# D_OUTPUT_RELAY.net
KiCad netlist of a schematic drawn in Altium Designer
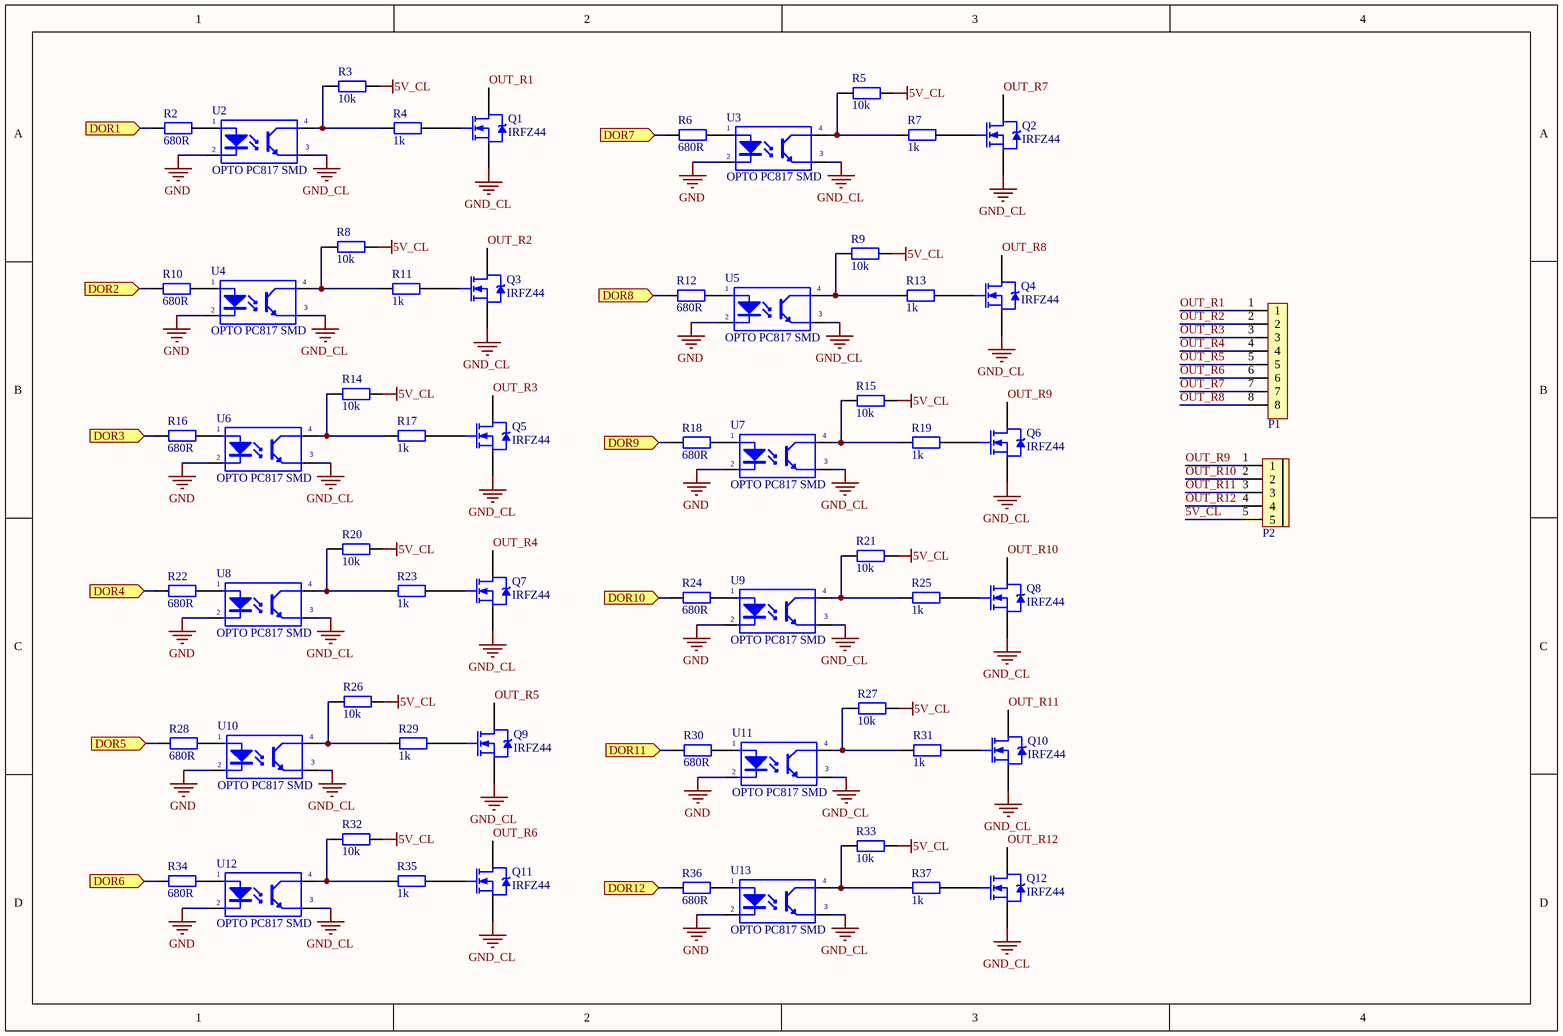
[diagram p0: D_OUTPUT_RELAY.SchDoc]

(export (version "E")
  (design (tool "Eeschema 10.0.6"))
  (components
    (comp (ref "P1")
      (value "CON 8 EDG5.08")
      (footprint "CON 8 8EDG5.08")
      (description "Cắm")
      (libsource (lib "Altium_Lib_by_KhueNguyenCreator") (part "CON 8 EDG5.08"))
    )
    (comp (ref "P2")
      (value "CON 5 EDG5.08")
      (footprint "CON 5 5EDG5.08")
      (description "Cắm")
      (libsource (lib "Altium_Lib_by_KhueNguyenCreator") (part "CON 5 EDG5.08"))
    )
    (comp (ref "Q1")
      (value "IRFZ44")
      (footprint "TO220")
      (description "N-Channel Power MOSFET")
      (libsource (lib "Altium_Lib_by_KhueNguyenCreator") (part "IRFZ44 DIP"))
    )
    (comp (ref "Q2")
      (value "IRFZ44")
      (footprint "TO220")
      (description "N-Channel Power MOSFET")
      (libsource (lib "Altium_Lib_by_KhueNguyenCreator") (part "IRFZ44 DIP"))
    )
    (comp (ref "Q3")
      (value "IRFZ44")
      (footprint "TO220")
      (description "N-Channel Power MOSFET")
      (libsource (lib "Altium_Lib_by_KhueNguyenCreator") (part "IRFZ44 DIP"))
    )
    (comp (ref "Q4")
      (value "IRFZ44")
      (footprint "TO220")
      (description "N-Channel Power MOSFET")
      (libsource (lib "Altium_Lib_by_KhueNguyenCreator") (part "IRFZ44 DIP"))
    )
    (comp (ref "Q5")
      (value "IRFZ44")
      (footprint "TO220")
      (description "N-Channel Power MOSFET")
      (libsource (lib "Altium_Lib_by_KhueNguyenCreator") (part "IRFZ44 DIP"))
    )
    (comp (ref "Q6")
      (value "IRFZ44")
      (footprint "TO220")
      (description "N-Channel Power MOSFET")
      (libsource (lib "Altium_Lib_by_KhueNguyenCreator") (part "IRFZ44 DIP"))
    )
    (comp (ref "Q7")
      (value "IRFZ44")
      (footprint "TO220")
      (description "N-Channel Power MOSFET")
      (libsource (lib "Altium_Lib_by_KhueNguyenCreator") (part "IRFZ44 DIP"))
    )
    (comp (ref "Q8")
      (value "IRFZ44")
      (footprint "TO220")
      (description "N-Channel Power MOSFET")
      (libsource (lib "Altium_Lib_by_KhueNguyenCreator") (part "IRFZ44 DIP"))
    )
    (comp (ref "Q9")
      (value "IRFZ44")
      (footprint "TO220")
      (description "N-Channel Power MOSFET")
      (libsource (lib "Altium_Lib_by_KhueNguyenCreator") (part "IRFZ44 DIP"))
    )
    (comp (ref "Q10")
      (value "IRFZ44")
      (footprint "TO220")
      (description "N-Channel Power MOSFET")
      (libsource (lib "Altium_Lib_by_KhueNguyenCreator") (part "IRFZ44 DIP"))
    )
    (comp (ref "Q11")
      (value "IRFZ44")
      (footprint "TO220")
      (description "N-Channel Power MOSFET")
      (libsource (lib "Altium_Lib_by_KhueNguyenCreator") (part "IRFZ44 DIP"))
    )
    (comp (ref "Q12")
      (value "IRFZ44")
      (footprint "TO220")
      (description "N-Channel Power MOSFET")
      (libsource (lib "Altium_Lib_by_KhueNguyenCreator") (part "IRFZ44 DIP"))
    )
    (comp (ref "R2")
      (value "680R")
      (footprint "tro smd 0805")
      (description "Dán")
      (libsource (lib "Altium_Lib_by_KhueNguyenCreator") (part "Tro 0805 1% 680R"))
    )
    (comp (ref "R3")
      (value "10k")
      (footprint "tro smd 0805")
      (description "Dán")
      (libsource (lib "Altium_Lib_by_KhueNguyenCreator") (part "Tro 0805 1% 10k"))
    )
    (comp (ref "R4")
      (value "1k")
      (footprint "tro smd 0805")
      (description "Dán")
      (libsource (lib "Altium_Lib_by_KhueNguyenCreator") (part "Tro 0805 1% 1k"))
    )
    (comp (ref "R5")
      (value "10k")
      (footprint "tro smd 0805")
      (description "Dán")
      (libsource (lib "Altium_Lib_by_KhueNguyenCreator") (part "Tro 0805 1% 10k"))
    )
    (comp (ref "R6")
      (value "680R")
      (footprint "tro smd 0805")
      (description "Dán")
      (libsource (lib "Altium_Lib_by_KhueNguyenCreator") (part "Tro 0805 1% 680R"))
    )
    (comp (ref "R7")
      (value "1k")
      (footprint "tro smd 0805")
      (description "Dán")
      (libsource (lib "Altium_Lib_by_KhueNguyenCreator") (part "Tro 0805 1% 1k"))
    )
    (comp (ref "R8")
      (value "10k")
      (footprint "tro smd 0805")
      (description "Dán")
      (libsource (lib "Altium_Lib_by_KhueNguyenCreator") (part "Tro 0805 1% 10k"))
    )
    (comp (ref "R9")
      (value "10k")
      (footprint "tro smd 0805")
      (description "Dán")
      (libsource (lib "Altium_Lib_by_KhueNguyenCreator") (part "Tro 0805 1% 10k"))
    )
    (comp (ref "R10")
      (value "680R")
      (footprint "tro smd 0805")
      (description "Dán")
      (libsource (lib "Altium_Lib_by_KhueNguyenCreator") (part "Tro 0805 1% 680R"))
    )
    (comp (ref "R11")
      (value "1k")
      (footprint "tro smd 0805")
      (description "Dán")
      (libsource (lib "Altium_Lib_by_KhueNguyenCreator") (part "Tro 0805 1% 1k"))
    )
    (comp (ref "R12")
      (value "680R")
      (footprint "tro smd 0805")
      (description "Dán")
      (libsource (lib "Altium_Lib_by_KhueNguyenCreator") (part "Tro 0805 1% 680R"))
    )
    (comp (ref "R13")
      (value "1k")
      (footprint "tro smd 0805")
      (description "Dán")
      (libsource (lib "Altium_Lib_by_KhueNguyenCreator") (part "Tro 0805 1% 1k"))
    )
    (comp (ref "R14")
      (value "10k")
      (footprint "tro smd 0805")
      (description "Dán")
      (libsource (lib "Altium_Lib_by_KhueNguyenCreator") (part "Tro 0805 1% 10k"))
    )
    (comp (ref "R15")
      (value "10k")
      (footprint "tro smd 0805")
      (description "Dán")
      (libsource (lib "Altium_Lib_by_KhueNguyenCreator") (part "Tro 0805 1% 10k"))
    )
    (comp (ref "R16")
      (value "680R")
      (footprint "tro smd 0805")
      (description "Dán")
      (libsource (lib "Altium_Lib_by_KhueNguyenCreator") (part "Tro 0805 1% 680R"))
    )
    (comp (ref "R17")
      (value "1k")
      (footprint "tro smd 0805")
      (description "Dán")
      (libsource (lib "Altium_Lib_by_KhueNguyenCreator") (part "Tro 0805 1% 1k"))
    )
    (comp (ref "R18")
      (value "680R")
      (footprint "tro smd 0805")
      (description "Dán")
      (libsource (lib "Altium_Lib_by_KhueNguyenCreator") (part "Tro 0805 1% 680R"))
    )
    (comp (ref "R19")
      (value "1k")
      (footprint "tro smd 0805")
      (description "Dán")
      (libsource (lib "Altium_Lib_by_KhueNguyenCreator") (part "Tro 0805 1% 1k"))
    )
    (comp (ref "R20")
      (value "10k")
      (footprint "tro smd 0805")
      (description "Dán")
      (libsource (lib "Altium_Lib_by_KhueNguyenCreator") (part "Tro 0805 1% 10k"))
    )
    (comp (ref "R21")
      (value "10k")
      (footprint "tro smd 0805")
      (description "Dán")
      (libsource (lib "Altium_Lib_by_KhueNguyenCreator") (part "Tro 0805 1% 10k"))
    )
    (comp (ref "R22")
      (value "680R")
      (footprint "tro smd 0805")
      (description "Dán")
      (libsource (lib "Altium_Lib_by_KhueNguyenCreator") (part "Tro 0805 1% 680R"))
    )
    (comp (ref "R23")
      (value "1k")
      (footprint "tro smd 0805")
      (description "Dán")
      (libsource (lib "Altium_Lib_by_KhueNguyenCreator") (part "Tro 0805 1% 1k"))
    )
    (comp (ref "R24")
      (value "680R")
      (footprint "tro smd 0805")
      (description "Dán")
      (libsource (lib "Altium_Lib_by_KhueNguyenCreator") (part "Tro 0805 1% 680R"))
    )
    (comp (ref "R25")
      (value "1k")
      (footprint "tro smd 0805")
      (description "Dán")
      (libsource (lib "Altium_Lib_by_KhueNguyenCreator") (part "Tro 0805 1% 1k"))
    )
    (comp (ref "R26")
      (value "10k")
      (footprint "tro smd 0805")
      (description "Dán")
      (libsource (lib "Altium_Lib_by_KhueNguyenCreator") (part "Tro 0805 1% 10k"))
    )
    (comp (ref "R27")
      (value "10k")
      (footprint "tro smd 0805")
      (description "Dán")
      (libsource (lib "Altium_Lib_by_KhueNguyenCreator") (part "Tro 0805 1% 10k"))
    )
    (comp (ref "R28")
      (value "680R")
      (footprint "tro smd 0805")
      (description "Dán")
      (libsource (lib "Altium_Lib_by_KhueNguyenCreator") (part "Tro 0805 1% 680R"))
    )
    (comp (ref "R29")
      (value "1k")
      (footprint "tro smd 0805")
      (description "Dán")
      (libsource (lib "Altium_Lib_by_KhueNguyenCreator") (part "Tro 0805 1% 1k"))
    )
    (comp (ref "R30")
      (value "680R")
      (footprint "tro smd 0805")
      (description "Dán")
      (libsource (lib "Altium_Lib_by_KhueNguyenCreator") (part "Tro 0805 1% 680R"))
    )
    (comp (ref "R31")
      (value "1k")
      (footprint "tro smd 0805")
      (description "Dán")
      (libsource (lib "Altium_Lib_by_KhueNguyenCreator") (part "Tro 0805 1% 1k"))
    )
    (comp (ref "R32")
      (value "10k")
      (footprint "tro smd 0805")
      (description "Dán")
      (libsource (lib "Altium_Lib_by_KhueNguyenCreator") (part "Tro 0805 1% 10k"))
    )
    (comp (ref "R33")
      (value "10k")
      (footprint "tro smd 0805")
      (description "Dán")
      (libsource (lib "Altium_Lib_by_KhueNguyenCreator") (part "Tro 0805 1% 10k"))
    )
    (comp (ref "R34")
      (value "680R")
      (footprint "tro smd 0805")
      (description "Dán")
      (libsource (lib "Altium_Lib_by_KhueNguyenCreator") (part "Tro 0805 1% 680R"))
    )
    (comp (ref "R35")
      (value "1k")
      (footprint "tro smd 0805")
      (description "Dán")
      (libsource (lib "Altium_Lib_by_KhueNguyenCreator") (part "Tro 0805 1% 1k"))
    )
    (comp (ref "R36")
      (value "680R")
      (footprint "tro smd 0805")
      (description "Dán")
      (libsource (lib "Altium_Lib_by_KhueNguyenCreator") (part "Tro 0805 1% 680R"))
    )
    (comp (ref "R37")
      (value "1k")
      (footprint "tro smd 0805")
      (description "Dán")
      (libsource (lib "Altium_Lib_by_KhueNguyenCreator") (part "Tro 0805 1% 1k"))
    )
    (comp (ref "U2")
      (value "OPTO PC817 SMD")
      (footprint "SOP4")
      (description "Single Opto")
      (libsource (lib "Altium_Lib_by_KhueNguyenCreator") (part "OPTO PC817 SMD"))
    )
    (comp (ref "U3")
      (value "OPTO PC817 SMD")
      (footprint "SOP4")
      (description "Single Opto")
      (libsource (lib "Altium_Lib_by_KhueNguyenCreator") (part "OPTO PC817 SMD"))
    )
    (comp (ref "U4")
      (value "OPTO PC817 SMD")
      (footprint "SOP4")
      (description "Single Opto")
      (libsource (lib "Altium_Lib_by_KhueNguyenCreator") (part "OPTO PC817 SMD"))
    )
    (comp (ref "U5")
      (value "OPTO PC817 SMD")
      (footprint "SOP4")
      (description "Single Opto")
      (libsource (lib "Altium_Lib_by_KhueNguyenCreator") (part "OPTO PC817 SMD"))
    )
    (comp (ref "U6")
      (value "OPTO PC817 SMD")
      (footprint "SOP4")
      (description "Single Opto")
      (libsource (lib "Altium_Lib_by_KhueNguyenCreator") (part "OPTO PC817 SMD"))
    )
    (comp (ref "U7")
      (value "OPTO PC817 SMD")
      (footprint "SOP4")
      (description "Single Opto")
      (libsource (lib "Altium_Lib_by_KhueNguyenCreator") (part "OPTO PC817 SMD"))
    )
    (comp (ref "U8")
      (value "OPTO PC817 SMD")
      (footprint "SOP4")
      (description "Single Opto")
      (libsource (lib "Altium_Lib_by_KhueNguyenCreator") (part "OPTO PC817 SMD"))
    )
    (comp (ref "U9")
      (value "OPTO PC817 SMD")
      (footprint "SOP4")
      (description "Single Opto")
      (libsource (lib "Altium_Lib_by_KhueNguyenCreator") (part "OPTO PC817 SMD"))
    )
    (comp (ref "U10")
      (value "OPTO PC817 SMD")
      (footprint "SOP4")
      (description "Single Opto")
      (libsource (lib "Altium_Lib_by_KhueNguyenCreator") (part "OPTO PC817 SMD"))
    )
    (comp (ref "U11")
      (value "OPTO PC817 SMD")
      (footprint "SOP4")
      (description "Single Opto")
      (libsource (lib "Altium_Lib_by_KhueNguyenCreator") (part "OPTO PC817 SMD"))
    )
    (comp (ref "U12")
      (value "OPTO PC817 SMD")
      (footprint "SOP4")
      (description "Single Opto")
      (libsource (lib "Altium_Lib_by_KhueNguyenCreator") (part "OPTO PC817 SMD"))
    )
    (comp (ref "U13")
      (value "OPTO PC817 SMD")
      (footprint "SOP4")
      (description "Single Opto")
      (libsource (lib "Altium_Lib_by_KhueNguyenCreator") (part "OPTO PC817 SMD"))
    )
  )
  (nets
    (net (code "1") (name "/DOR1") (class "Default")
      (node (ref "R2") (pin "1") (pinfunction "1_1") (pintype "passive"))
    )
    (net (code "2") (name "/DOR2") (class "Default")
      (node (ref "R10") (pin "1") (pinfunction "1_1") (pintype "passive"))
    )
    (net (code "3") (name "/DOR3") (class "Default")
      (node (ref "R16") (pin "1") (pinfunction "1_1") (pintype "passive"))
    )
    (net (code "4") (name "/DOR4") (class "Default")
      (node (ref "R22") (pin "1") (pinfunction "1_1") (pintype "passive"))
    )
    (net (code "5") (name "/DOR5") (class "Default")
      (node (ref "R28") (pin "1") (pinfunction "1_1") (pintype "passive"))
    )
    (net (code "6") (name "/DOR6") (class "Default")
      (node (ref "R34") (pin "1") (pinfunction "1_1") (pintype "passive"))
    )
    (net (code "7") (name "/DOR7") (class "Default")
      (node (ref "R6") (pin "1") (pinfunction "1_1") (pintype "passive"))
    )
    (net (code "8") (name "/DOR8") (class "Default")
      (node (ref "R12") (pin "1") (pinfunction "1_1") (pintype "passive"))
    )
    (net (code "9") (name "/DOR9") (class "Default")
      (node (ref "R18") (pin "1") (pinfunction "1_1") (pintype "passive"))
    )
    (net (code "10") (name "/DOR10") (class "Default")
      (node (ref "R24") (pin "1") (pinfunction "1_1") (pintype "passive"))
    )
    (net (code "11") (name "/DOR11") (class "Default")
      (node (ref "R30") (pin "1") (pinfunction "1_1") (pintype "passive"))
    )
    (net (code "12") (name "/DOR12") (class "Default")
      (node (ref "R36") (pin "1") (pinfunction "1_1") (pintype "passive"))
    )
    (net (code "13") (name "/OUT_R1") (class "Default")
      (node (ref "P1") (pin "1") (pinfunction "1_1") (pintype "passive"))
      (node (ref "Q1") (pin "2") (pinfunction "D_2") (pintype "passive"))
    )
    (net (code "14") (name "/OUT_R2") (class "Default")
      (node (ref "P1") (pin "2") (pinfunction "2_2") (pintype "passive"))
      (node (ref "Q3") (pin "2") (pinfunction "D_2") (pintype "passive"))
    )
    (net (code "15") (name "/OUT_R3") (class "Default")
      (node (ref "P1") (pin "3") (pinfunction "3_3") (pintype "passive"))
      (node (ref "Q5") (pin "2") (pinfunction "D_2") (pintype "passive"))
    )
    (net (code "16") (name "/OUT_R4") (class "Default")
      (node (ref "P1") (pin "4") (pinfunction "4_4") (pintype "passive"))
      (node (ref "Q7") (pin "2") (pinfunction "D_2") (pintype "passive"))
    )
    (net (code "17") (name "/OUT_R5") (class "Default")
      (node (ref "P1") (pin "5") (pinfunction "5_5") (pintype "passive"))
      (node (ref "Q9") (pin "2") (pinfunction "D_2") (pintype "passive"))
    )
    (net (code "18") (name "/OUT_R6") (class "Default")
      (node (ref "P1") (pin "6") (pinfunction "6_6") (pintype "passive"))
      (node (ref "Q11") (pin "2") (pinfunction "D_2") (pintype "passive"))
    )
    (net (code "19") (name "/OUT_R7") (class "Default")
      (node (ref "P1") (pin "7") (pinfunction "7_7") (pintype "passive"))
      (node (ref "Q2") (pin "2") (pinfunction "D_2") (pintype "passive"))
    )
    (net (code "20") (name "/OUT_R8") (class "Default")
      (node (ref "P1") (pin "8") (pinfunction "8_8") (pintype "passive"))
      (node (ref "Q4") (pin "2") (pinfunction "D_2") (pintype "passive"))
    )
    (net (code "21") (name "/OUT_R9") (class "Default")
      (node (ref "P2") (pin "1") (pinfunction "1_1") (pintype "passive"))
      (node (ref "Q6") (pin "2") (pinfunction "D_2") (pintype "passive"))
    )
    (net (code "22") (name "/OUT_R10") (class "Default")
      (node (ref "P2") (pin "2") (pinfunction "2_2") (pintype "passive"))
      (node (ref "Q8") (pin "2") (pinfunction "D_2") (pintype "passive"))
    )
    (net (code "23") (name "/OUT_R11") (class "Default")
      (node (ref "P2") (pin "3") (pinfunction "3_3") (pintype "passive"))
      (node (ref "Q10") (pin "2") (pinfunction "D_2") (pintype "passive"))
    )
    (net (code "24") (name "/OUT_R12") (class "Default")
      (node (ref "P2") (pin "4") (pinfunction "4_4") (pintype "passive"))
      (node (ref "Q12") (pin "2") (pinfunction "D_2") (pintype "passive"))
    )
    (net (code "25") (name "5V_CL") (class "Default")
      (node (ref "P2") (pin "5") (pinfunction "5_5") (pintype "passive"))
      (node (ref "R14") (pin "1") (pinfunction "1_1") (pintype "passive"))
      (node (ref "R15") (pin "1") (pinfunction "1_1") (pintype "passive"))
      (node (ref "R20") (pin "1") (pinfunction "1_1") (pintype "passive"))
      (node (ref "R21") (pin "1") (pinfunction "1_1") (pintype "passive"))
      (node (ref "R26") (pin "1") (pinfunction "1_1") (pintype "passive"))
      (node (ref "R27") (pin "1") (pinfunction "1_1") (pintype "passive"))
      (node (ref "R3") (pin "1") (pinfunction "1_1") (pintype "passive"))
      (node (ref "R32") (pin "1") (pinfunction "1_1") (pintype "passive"))
      (node (ref "R33") (pin "1") (pinfunction "1_1") (pintype "passive"))
      (node (ref "R5") (pin "1") (pinfunction "1_1") (pintype "passive"))
      (node (ref "R8") (pin "1") (pinfunction "1_1") (pintype "passive"))
      (node (ref "R9") (pin "1") (pinfunction "1_1") (pintype "passive"))
    )
    (net (code "26") (name "GND") (class "Default")
      (node (ref "U10") (pin "2") (pinfunction "K_2") (pintype "passive"))
      (node (ref "U11") (pin "2") (pinfunction "K_2") (pintype "passive"))
      (node (ref "U12") (pin "2") (pinfunction "K_2") (pintype "passive"))
      (node (ref "U13") (pin "2") (pinfunction "K_2") (pintype "passive"))
      (node (ref "U2") (pin "2") (pinfunction "K_2") (pintype "passive"))
      (node (ref "U3") (pin "2") (pinfunction "K_2") (pintype "passive"))
      (node (ref "U4") (pin "2") (pinfunction "K_2") (pintype "passive"))
      (node (ref "U5") (pin "2") (pinfunction "K_2") (pintype "passive"))
      (node (ref "U6") (pin "2") (pinfunction "K_2") (pintype "passive"))
      (node (ref "U7") (pin "2") (pinfunction "K_2") (pintype "passive"))
      (node (ref "U8") (pin "2") (pinfunction "K_2") (pintype "passive"))
      (node (ref "U9") (pin "2") (pinfunction "K_2") (pintype "passive"))
    )
    (net (code "27") (name "GND_CL") (class "Default")
      (node (ref "Q1") (pin "3") (pinfunction "S_3") (pintype "passive"))
      (node (ref "Q10") (pin "3") (pinfunction "S_3") (pintype "passive"))
      (node (ref "Q11") (pin "3") (pinfunction "S_3") (pintype "passive"))
      (node (ref "Q12") (pin "3") (pinfunction "S_3") (pintype "passive"))
      (node (ref "Q2") (pin "3") (pinfunction "S_3") (pintype "passive"))
      (node (ref "Q3") (pin "3") (pinfunction "S_3") (pintype "passive"))
      (node (ref "Q4") (pin "3") (pinfunction "S_3") (pintype "passive"))
      (node (ref "Q5") (pin "3") (pinfunction "S_3") (pintype "passive"))
      (node (ref "Q6") (pin "3") (pinfunction "S_3") (pintype "passive"))
      (node (ref "Q7") (pin "3") (pinfunction "S_3") (pintype "passive"))
      (node (ref "Q8") (pin "3") (pinfunction "S_3") (pintype "passive"))
      (node (ref "Q9") (pin "3") (pinfunction "S_3") (pintype "passive"))
      (node (ref "U10") (pin "3") (pinfunction "E_3") (pintype "passive"))
      (node (ref "U11") (pin "3") (pinfunction "E_3") (pintype "passive"))
      (node (ref "U12") (pin "3") (pinfunction "E_3") (pintype "passive"))
      (node (ref "U13") (pin "3") (pinfunction "E_3") (pintype "passive"))
      (node (ref "U2") (pin "3") (pinfunction "E_3") (pintype "passive"))
      (node (ref "U3") (pin "3") (pinfunction "E_3") (pintype "passive"))
      (node (ref "U4") (pin "3") (pinfunction "E_3") (pintype "passive"))
      (node (ref "U5") (pin "3") (pinfunction "E_3") (pintype "passive"))
      (node (ref "U6") (pin "3") (pinfunction "E_3") (pintype "passive"))
      (node (ref "U7") (pin "3") (pinfunction "E_3") (pintype "passive"))
      (node (ref "U8") (pin "3") (pinfunction "E_3") (pintype "passive"))
      (node (ref "U9") (pin "3") (pinfunction "E_3") (pintype "passive"))
    )
    (net (code "28") (name "Net-(Q1-G)") (class "Default")
      (node (ref "Q1") (pin "1") (pinfunction "G_1") (pintype "passive"))
      (node (ref "R4") (pin "2") (pinfunction "2_2") (pintype "passive"))
    )
    (net (code "29") (name "Net-(Q2-G)") (class "Default")
      (node (ref "Q2") (pin "1") (pinfunction "G_1") (pintype "passive"))
      (node (ref "R7") (pin "2") (pinfunction "2_2") (pintype "passive"))
    )
    (net (code "30") (name "Net-(Q3-G)") (class "Default")
      (node (ref "Q3") (pin "1") (pinfunction "G_1") (pintype "passive"))
      (node (ref "R11") (pin "2") (pinfunction "2_2") (pintype "passive"))
    )
    (net (code "31") (name "Net-(Q4-G)") (class "Default")
      (node (ref "Q4") (pin "1") (pinfunction "G_1") (pintype "passive"))
      (node (ref "R13") (pin "2") (pinfunction "2_2") (pintype "passive"))
    )
    (net (code "32") (name "Net-(Q5-G)") (class "Default")
      (node (ref "Q5") (pin "1") (pinfunction "G_1") (pintype "passive"))
      (node (ref "R17") (pin "2") (pinfunction "2_2") (pintype "passive"))
    )
    (net (code "33") (name "Net-(Q6-G)") (class "Default")
      (node (ref "Q6") (pin "1") (pinfunction "G_1") (pintype "passive"))
      (node (ref "R19") (pin "2") (pinfunction "2_2") (pintype "passive"))
    )
    (net (code "34") (name "Net-(Q7-G)") (class "Default")
      (node (ref "Q7") (pin "1") (pinfunction "G_1") (pintype "passive"))
      (node (ref "R23") (pin "2") (pinfunction "2_2") (pintype "passive"))
    )
    (net (code "35") (name "Net-(Q8-G)") (class "Default")
      (node (ref "Q8") (pin "1") (pinfunction "G_1") (pintype "passive"))
      (node (ref "R25") (pin "2") (pinfunction "2_2") (pintype "passive"))
    )
    (net (code "36") (name "Net-(Q9-G)") (class "Default")
      (node (ref "Q9") (pin "1") (pinfunction "G_1") (pintype "passive"))
      (node (ref "R29") (pin "2") (pinfunction "2_2") (pintype "passive"))
    )
    (net (code "37") (name "Net-(Q10-G)") (class "Default")
      (node (ref "Q10") (pin "1") (pinfunction "G_1") (pintype "passive"))
      (node (ref "R31") (pin "2") (pinfunction "2_2") (pintype "passive"))
    )
    (net (code "38") (name "Net-(Q11-G)") (class "Default")
      (node (ref "Q11") (pin "1") (pinfunction "G_1") (pintype "passive"))
      (node (ref "R35") (pin "2") (pinfunction "2_2") (pintype "passive"))
    )
    (net (code "39") (name "Net-(Q12-G)") (class "Default")
      (node (ref "Q12") (pin "1") (pinfunction "G_1") (pintype "passive"))
      (node (ref "R37") (pin "2") (pinfunction "2_2") (pintype "passive"))
    )
    (net (code "40") (name "Net-(U2-A)") (class "Default")
      (node (ref "R2") (pin "2") (pinfunction "2_2") (pintype "passive"))
      (node (ref "U2") (pin "1") (pinfunction "A_1") (pintype "passive"))
    )
    (net (code "41") (name "Net-(U2-C)") (class "Default")
      (node (ref "R3") (pin "2") (pinfunction "2_2") (pintype "passive"))
      (node (ref "R4") (pin "1") (pinfunction "1_1") (pintype "passive"))
      (node (ref "U2") (pin "4") (pinfunction "C_4") (pintype "passive"))
    )
    (net (code "42") (name "Net-(U3-A)") (class "Default")
      (node (ref "R6") (pin "2") (pinfunction "2_2") (pintype "passive"))
      (node (ref "U3") (pin "1") (pinfunction "A_1") (pintype "passive"))
    )
    (net (code "43") (name "Net-(U3-C)") (class "Default")
      (node (ref "R5") (pin "2") (pinfunction "2_2") (pintype "passive"))
      (node (ref "R7") (pin "1") (pinfunction "1_1") (pintype "passive"))
      (node (ref "U3") (pin "4") (pinfunction "C_4") (pintype "passive"))
    )
    (net (code "44") (name "Net-(U4-A)") (class "Default")
      (node (ref "R10") (pin "2") (pinfunction "2_2") (pintype "passive"))
      (node (ref "U4") (pin "1") (pinfunction "A_1") (pintype "passive"))
    )
    (net (code "45") (name "Net-(U4-C)") (class "Default")
      (node (ref "R11") (pin "1") (pinfunction "1_1") (pintype "passive"))
      (node (ref "R8") (pin "2") (pinfunction "2_2") (pintype "passive"))
      (node (ref "U4") (pin "4") (pinfunction "C_4") (pintype "passive"))
    )
    (net (code "46") (name "Net-(U5-A)") (class "Default")
      (node (ref "R12") (pin "2") (pinfunction "2_2") (pintype "passive"))
      (node (ref "U5") (pin "1") (pinfunction "A_1") (pintype "passive"))
    )
    (net (code "47") (name "Net-(U5-C)") (class "Default")
      (node (ref "R13") (pin "1") (pinfunction "1_1") (pintype "passive"))
      (node (ref "R9") (pin "2") (pinfunction "2_2") (pintype "passive"))
      (node (ref "U5") (pin "4") (pinfunction "C_4") (pintype "passive"))
    )
    (net (code "48") (name "Net-(U6-A)") (class "Default")
      (node (ref "R16") (pin "2") (pinfunction "2_2") (pintype "passive"))
      (node (ref "U6") (pin "1") (pinfunction "A_1") (pintype "passive"))
    )
    (net (code "49") (name "Net-(U6-C)") (class "Default")
      (node (ref "R14") (pin "2") (pinfunction "2_2") (pintype "passive"))
      (node (ref "R17") (pin "1") (pinfunction "1_1") (pintype "passive"))
      (node (ref "U6") (pin "4") (pinfunction "C_4") (pintype "passive"))
    )
    (net (code "50") (name "Net-(U7-A)") (class "Default")
      (node (ref "R18") (pin "2") (pinfunction "2_2") (pintype "passive"))
      (node (ref "U7") (pin "1") (pinfunction "A_1") (pintype "passive"))
    )
    (net (code "51") (name "Net-(U7-C)") (class "Default")
      (node (ref "R15") (pin "2") (pinfunction "2_2") (pintype "passive"))
      (node (ref "R19") (pin "1") (pinfunction "1_1") (pintype "passive"))
      (node (ref "U7") (pin "4") (pinfunction "C_4") (pintype "passive"))
    )
    (net (code "52") (name "Net-(U8-A)") (class "Default")
      (node (ref "R22") (pin "2") (pinfunction "2_2") (pintype "passive"))
      (node (ref "U8") (pin "1") (pinfunction "A_1") (pintype "passive"))
    )
    (net (code "53") (name "Net-(U8-C)") (class "Default")
      (node (ref "R20") (pin "2") (pinfunction "2_2") (pintype "passive"))
      (node (ref "R23") (pin "1") (pinfunction "1_1") (pintype "passive"))
      (node (ref "U8") (pin "4") (pinfunction "C_4") (pintype "passive"))
    )
    (net (code "54") (name "Net-(U9-A)") (class "Default")
      (node (ref "R24") (pin "2") (pinfunction "2_2") (pintype "passive"))
      (node (ref "U9") (pin "1") (pinfunction "A_1") (pintype "passive"))
    )
    (net (code "55") (name "Net-(U9-C)") (class "Default")
      (node (ref "R21") (pin "2") (pinfunction "2_2") (pintype "passive"))
      (node (ref "R25") (pin "1") (pinfunction "1_1") (pintype "passive"))
      (node (ref "U9") (pin "4") (pinfunction "C_4") (pintype "passive"))
    )
    (net (code "56") (name "Net-(U10-A)") (class "Default")
      (node (ref "R28") (pin "2") (pinfunction "2_2") (pintype "passive"))
      (node (ref "U10") (pin "1") (pinfunction "A_1") (pintype "passive"))
    )
    (net (code "57") (name "Net-(U10-C)") (class "Default")
      (node (ref "R26") (pin "2") (pinfunction "2_2") (pintype "passive"))
      (node (ref "R29") (pin "1") (pinfunction "1_1") (pintype "passive"))
      (node (ref "U10") (pin "4") (pinfunction "C_4") (pintype "passive"))
    )
    (net (code "58") (name "Net-(U11-A)") (class "Default")
      (node (ref "R30") (pin "2") (pinfunction "2_2") (pintype "passive"))
      (node (ref "U11") (pin "1") (pinfunction "A_1") (pintype "passive"))
    )
    (net (code "59") (name "Net-(U11-C)") (class "Default")
      (node (ref "R27") (pin "2") (pinfunction "2_2") (pintype "passive"))
      (node (ref "R31") (pin "1") (pinfunction "1_1") (pintype "passive"))
      (node (ref "U11") (pin "4") (pinfunction "C_4") (pintype "passive"))
    )
    (net (code "60") (name "Net-(U12-A)") (class "Default")
      (node (ref "R34") (pin "2") (pinfunction "2_2") (pintype "passive"))
      (node (ref "U12") (pin "1") (pinfunction "A_1") (pintype "passive"))
    )
    (net (code "61") (name "Net-(U12-C)") (class "Default")
      (node (ref "R32") (pin "2") (pinfunction "2_2") (pintype "passive"))
      (node (ref "R35") (pin "1") (pinfunction "1_1") (pintype "passive"))
      (node (ref "U12") (pin "4") (pinfunction "C_4") (pintype "passive"))
    )
    (net (code "62") (name "Net-(U13-A)") (class "Default")
      (node (ref "R36") (pin "2") (pinfunction "2_2") (pintype "passive"))
      (node (ref "U13") (pin "1") (pinfunction "A_1") (pintype "passive"))
    )
    (net (code "63") (name "Net-(U13-C)") (class "Default")
      (node (ref "R33") (pin "2") (pinfunction "2_2") (pintype "passive"))
      (node (ref "R37") (pin "1") (pinfunction "1_1") (pintype "passive"))
      (node (ref "U13") (pin "4") (pinfunction "C_4") (pintype "passive"))
    )
  )
)
